# RLY_1_0.net
KiCad netlist of a schematic drawn in EAGLE
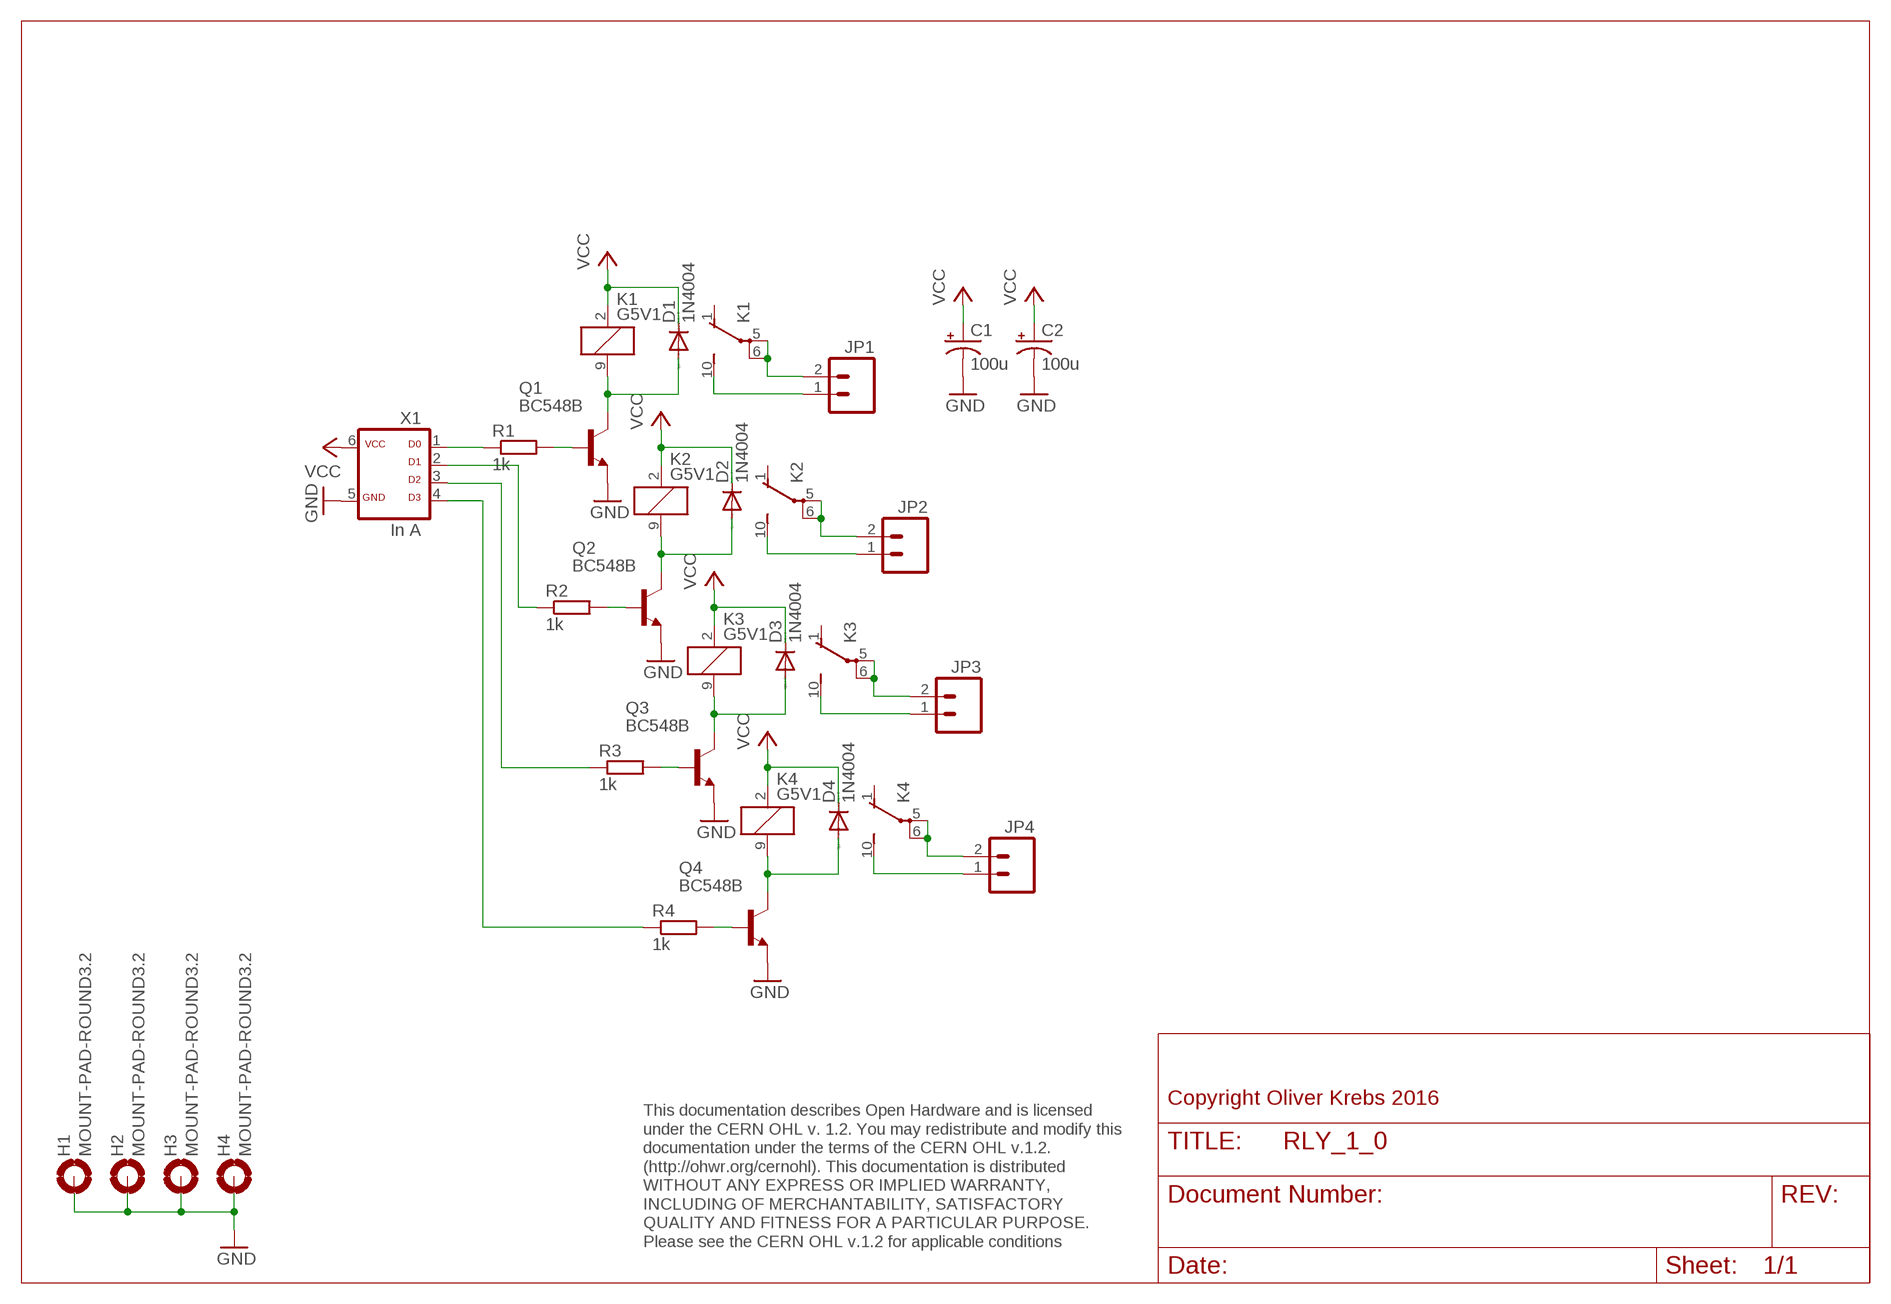
[diagram p0: schematic, sheet 1]

(export (version "E")
  (design (tool "Eeschema 10.0.6"))
  (components
    (comp (ref "C1")
      (value "100u")
      (footprint "eagle-import:CPOL-RADIAL-100UF-25V")
      (libsource (lib "eagle-import") (part "CAP_POLPTH1"))
    )
    (comp (ref "C2")
      (value "100u")
      (footprint "eagle-import:CPOL-RADIAL-100UF-25V")
      (libsource (lib "eagle-import") (part "CAP_POLPTH1"))
    )
    (comp (ref "D1")
      (value "1N4004")
      (footprint "eagle-import:DO41-10")
      (libsource (lib "eagle-import") (part "1N4004"))
    )
    (comp (ref "D2")
      (value "1N4004")
      (footprint "eagle-import:DO41-10")
      (libsource (lib "eagle-import") (part "1N4004"))
    )
    (comp (ref "D3")
      (value "1N4004")
      (footprint "eagle-import:DO41-10")
      (libsource (lib "eagle-import") (part "1N4004"))
    )
    (comp (ref "D4")
      (value "1N4004")
      (footprint "eagle-import:DO41-10")
      (libsource (lib "eagle-import") (part "1N4004"))
    )
    (comp (ref "H1")
      (value "MOUNT-PAD-ROUND3.2")
      (footprint "eagle-import:3,2-PAD")
      (libsource (lib "eagle-import") (part "MOUNT-PAD-ROUND3.2"))
    )
    (comp (ref "H2")
      (value "MOUNT-PAD-ROUND3.2")
      (footprint "eagle-import:3,2-PAD")
      (libsource (lib "eagle-import") (part "MOUNT-PAD-ROUND3.2"))
    )
    (comp (ref "H3")
      (value "MOUNT-PAD-ROUND3.2")
      (footprint "eagle-import:3,2-PAD")
      (libsource (lib "eagle-import") (part "MOUNT-PAD-ROUND3.2"))
    )
    (comp (ref "H4")
      (value "MOUNT-PAD-ROUND3.2")
      (footprint "eagle-import:3,2-PAD")
      (libsource (lib "eagle-import") (part "MOUNT-PAD-ROUND3.2"))
    )
    (comp (ref "JP1")
      (value "M021.3MM-5.08")
      (footprint "eagle-import:1X02_BIG_5.08")
      (libsource (lib "eagle-import") (part "M021.3MM-5.08"))
    )
    (comp (ref "JP2")
      (value "M021.3MM-5.08")
      (footprint "eagle-import:1X02_BIG_5.08")
      (libsource (lib "eagle-import") (part "M021.3MM-5.08"))
    )
    (comp (ref "JP3")
      (value "M021.3MM-5.08")
      (footprint "eagle-import:1X02_BIG_5.08")
      (libsource (lib "eagle-import") (part "M021.3MM-5.08"))
    )
    (comp (ref "JP4")
      (value "M021.3MM-5.08")
      (footprint "eagle-import:1X02_BIG_5.08")
      (libsource (lib "eagle-import") (part "M021.3MM-5.08"))
    )
    (comp (ref "K1")
      (value "G5V1")
      (footprint "eagle-import:G5V1")
      (fields (field (name "MPN") "G5V-1-DC24"))
      (libsource (lib "eagle-import") (part "G5V1"))
    )
    (comp (ref "K2")
      (value "G5V1")
      (footprint "eagle-import:G5V1")
      (fields (field (name "MPN") "G5V-1-DC24"))
      (libsource (lib "eagle-import") (part "G5V1"))
    )
    (comp (ref "K3")
      (value "G5V1")
      (footprint "eagle-import:G5V1")
      (fields (field (name "MPN") "G5V-1-DC24"))
      (libsource (lib "eagle-import") (part "G5V1"))
    )
    (comp (ref "K4")
      (value "G5V1")
      (footprint "eagle-import:G5V1")
      (fields (field (name "MPN") "G5V-1-DC24"))
      (libsource (lib "eagle-import") (part "G5V1"))
    )
    (comp (ref "Q1")
      (value "BC548B")
      (footprint "eagle-import:TO92-EBC")
      (libsource (lib "eagle-import") (part "BC548B"))
    )
    (comp (ref "Q2")
      (value "BC548B")
      (footprint "eagle-import:TO92-EBC")
      (libsource (lib "eagle-import") (part "BC548B"))
    )
    (comp (ref "Q3")
      (value "BC548B")
      (footprint "eagle-import:TO92-EBC")
      (libsource (lib "eagle-import") (part "BC548B"))
    )
    (comp (ref "Q4")
      (value "BC548B")
      (footprint "eagle-import:TO92-EBC")
      (libsource (lib "eagle-import") (part "BC548B"))
    )
    (comp (ref "R1")
      (value "1k")
      (footprint "eagle-import:0207_10")
      (libsource (lib "eagle-import") (part "R-EU_0207/10"))
    )
    (comp (ref "R2")
      (value "1k")
      (footprint "eagle-import:0207_10")
      (libsource (lib "eagle-import") (part "R-EU_0207/10"))
    )
    (comp (ref "R3")
      (value "1k")
      (footprint "eagle-import:0207_10")
      (libsource (lib "eagle-import") (part "R-EU_0207/10"))
    )
    (comp (ref "R4")
      (value "1k")
      (footprint "eagle-import:0207_10")
      (libsource (lib "eagle-import") (part "R-EU_0207/10"))
    )
    (comp (ref "X1")
      (value "In A")
      (footprint "eagle-import:ML-6")
      (libsource (lib "eagle-import") (part "ML6D"))
    )
  )
  (nets
    (net (code "1") (name "GND") (class "Default")
      (node (ref "C1") (pin "2") (pinfunction "-_2") (pintype "passive"))
      (node (ref "C2") (pin "2") (pinfunction "-_2") (pintype "passive"))
      (node (ref "H1") (pin "B3,2") (pinfunction "MOUNT_B3,2") (pintype "passive"))
      (node (ref "H2") (pin "B3,2") (pinfunction "MOUNT_B3,2") (pintype "passive"))
      (node (ref "H3") (pin "B3,2") (pinfunction "MOUNT_B3,2") (pintype "passive"))
      (node (ref "H4") (pin "B3,2") (pinfunction "MOUNT_B3,2") (pintype "passive"))
      (node (ref "Q1") (pin "E") (pinfunction "E_E") (pintype "passive"))
      (node (ref "Q2") (pin "E") (pinfunction "E_E") (pintype "passive"))
      (node (ref "Q3") (pin "E") (pinfunction "E_E") (pintype "passive"))
      (node (ref "Q4") (pin "E") (pinfunction "E_E") (pintype "passive"))
      (node (ref "X1") (pin "5") (pinfunction "5_5") (pintype "passive"))
    )
    (net (code "2") (name "Net-(JP1-Pad2)") (class "Default")
      (node (ref "JP1") (pin "2") (pinfunction "2_2") (pintype "passive"))
      (node (ref "K1") (pin "5") (pinfunction "P_5") (pintype "passive"))
      (node (ref "K1") (pin "6") (pinfunction "P_6") (pintype "passive"))
    )
    (net (code "3") (name "Net-(JP2-Pad2)") (class "Default")
      (node (ref "JP2") (pin "2") (pinfunction "2_2") (pintype "passive"))
      (node (ref "K2") (pin "5") (pinfunction "P_5") (pintype "passive"))
      (node (ref "K2") (pin "6") (pinfunction "P_6") (pintype "passive"))
    )
    (net (code "4") (name "Net-(JP3-Pad2)") (class "Default")
      (node (ref "JP3") (pin "2") (pinfunction "2_2") (pintype "passive"))
      (node (ref "K3") (pin "5") (pinfunction "P_5") (pintype "passive"))
      (node (ref "K3") (pin "6") (pinfunction "P_6") (pintype "passive"))
    )
    (net (code "5") (name "Net-(JP4-Pad2)") (class "Default")
      (node (ref "JP4") (pin "2") (pinfunction "2_2") (pintype "passive"))
      (node (ref "K4") (pin "5") (pinfunction "P_5") (pintype "passive"))
      (node (ref "K4") (pin "6") (pinfunction "P_6") (pintype "passive"))
    )
    (net (code "6") (name "Net-(K1A-2)") (class "Default")
      (node (ref "D1") (pin "A") (pinfunction "A_A") (pintype "passive"))
      (node (ref "K1") (pin "9") (pinfunction "2_9") (pintype "passive"))
      (node (ref "Q1") (pin "C") (pinfunction "C_C") (pintype "passive"))
    )
    (net (code "7") (name "Net-(K1B-S)") (class "Default")
      (node (ref "JP1") (pin "1") (pinfunction "1_1") (pintype "passive"))
      (node (ref "K1") (pin "10") (pinfunction "S_10") (pintype "passive"))
    )
    (net (code "8") (name "Net-(K2A-2)") (class "Default")
      (node (ref "D2") (pin "A") (pinfunction "A_A") (pintype "passive"))
      (node (ref "K2") (pin "9") (pinfunction "2_9") (pintype "passive"))
      (node (ref "Q2") (pin "C") (pinfunction "C_C") (pintype "passive"))
    )
    (net (code "9") (name "Net-(K2B-S)") (class "Default")
      (node (ref "JP2") (pin "1") (pinfunction "1_1") (pintype "passive"))
      (node (ref "K2") (pin "10") (pinfunction "S_10") (pintype "passive"))
    )
    (net (code "10") (name "Net-(K3A-2)") (class "Default")
      (node (ref "D3") (pin "A") (pinfunction "A_A") (pintype "passive"))
      (node (ref "K3") (pin "9") (pinfunction "2_9") (pintype "passive"))
      (node (ref "Q3") (pin "C") (pinfunction "C_C") (pintype "passive"))
    )
    (net (code "11") (name "Net-(K3B-S)") (class "Default")
      (node (ref "JP3") (pin "1") (pinfunction "1_1") (pintype "passive"))
      (node (ref "K3") (pin "10") (pinfunction "S_10") (pintype "passive"))
    )
    (net (code "12") (name "Net-(K4A-2)") (class "Default")
      (node (ref "D4") (pin "A") (pinfunction "A_A") (pintype "passive"))
      (node (ref "K4") (pin "9") (pinfunction "2_9") (pintype "passive"))
      (node (ref "Q4") (pin "C") (pinfunction "C_C") (pintype "passive"))
    )
    (net (code "13") (name "Net-(K4B-S)") (class "Default")
      (node (ref "JP4") (pin "1") (pinfunction "1_1") (pintype "passive"))
      (node (ref "K4") (pin "10") (pinfunction "S_10") (pintype "passive"))
    )
    (net (code "14") (name "Net-(Q1-PadB)") (class "Default")
      (node (ref "Q1") (pin "B") (pinfunction "B_B") (pintype "passive"))
      (node (ref "R1") (pin "2") (pinfunction "2_2") (pintype "passive"))
    )
    (net (code "15") (name "Net-(Q2-PadB)") (class "Default")
      (node (ref "Q2") (pin "B") (pinfunction "B_B") (pintype "passive"))
      (node (ref "R2") (pin "2") (pinfunction "2_2") (pintype "passive"))
    )
    (net (code "16") (name "Net-(Q3-PadB)") (class "Default")
      (node (ref "Q3") (pin "B") (pinfunction "B_B") (pintype "passive"))
      (node (ref "R3") (pin "2") (pinfunction "2_2") (pintype "passive"))
    )
    (net (code "17") (name "Net-(Q4-PadB)") (class "Default")
      (node (ref "Q4") (pin "B") (pinfunction "B_B") (pintype "passive"))
      (node (ref "R4") (pin "2") (pinfunction "2_2") (pintype "passive"))
    )
    (net (code "18") (name "Net-(R1-Pad1)") (class "Default")
      (node (ref "R1") (pin "1") (pinfunction "1_1") (pintype "passive"))
      (node (ref "X1") (pin "1") (pinfunction "1_1") (pintype "passive"))
    )
    (net (code "19") (name "Net-(R2-Pad1)") (class "Default")
      (node (ref "R2") (pin "1") (pinfunction "1_1") (pintype "passive"))
      (node (ref "X1") (pin "2") (pinfunction "2_2") (pintype "passive"))
    )
    (net (code "20") (name "Net-(R3-Pad1)") (class "Default")
      (node (ref "R3") (pin "1") (pinfunction "1_1") (pintype "passive"))
      (node (ref "X1") (pin "3") (pinfunction "3_3") (pintype "passive"))
    )
    (net (code "21") (name "Net-(R4-Pad1)") (class "Default")
      (node (ref "R4") (pin "1") (pinfunction "1_1") (pintype "passive"))
      (node (ref "X1") (pin "4") (pinfunction "4_4") (pintype "passive"))
    )
    (net (code "22") (name "VCC") (class "Default")
      (node (ref "C1") (pin "1") (pinfunction "+_1") (pintype "passive"))
      (node (ref "C2") (pin "1") (pinfunction "+_1") (pintype "passive"))
      (node (ref "D1") (pin "C") (pinfunction "C_C") (pintype "passive"))
      (node (ref "D2") (pin "C") (pinfunction "C_C") (pintype "passive"))
      (node (ref "D3") (pin "C") (pinfunction "C_C") (pintype "passive"))
      (node (ref "D4") (pin "C") (pinfunction "C_C") (pintype "passive"))
      (node (ref "K1") (pin "2") (pinfunction "1_2") (pintype "passive"))
      (node (ref "K2") (pin "2") (pinfunction "1_2") (pintype "passive"))
      (node (ref "K3") (pin "2") (pinfunction "1_2") (pintype "passive"))
      (node (ref "K4") (pin "2") (pinfunction "1_2") (pintype "passive"))
      (node (ref "X1") (pin "6") (pinfunction "6_6") (pintype "passive"))
    )
    (net (code "23") (name "unconnected-(K1B-O-Pad1)") (class "Default")
      (node (ref "K1") (pin "1") (pinfunction "O_1") (pintype "passive"))
    )
    (net (code "24") (name "unconnected-(K2B-O-Pad1)") (class "Default")
      (node (ref "K2") (pin "1") (pinfunction "O_1") (pintype "passive"))
    )
    (net (code "25") (name "unconnected-(K3B-O-Pad1)") (class "Default")
      (node (ref "K3") (pin "1") (pinfunction "O_1") (pintype "passive"))
    )
    (net (code "26") (name "unconnected-(K4B-O-Pad1)") (class "Default")
      (node (ref "K4") (pin "1") (pinfunction "O_1") (pintype "passive"))
    )
  )
)
